# 20210410-JGaylord-Exprsn_MIDI.net
KiCad netlist of a schematic drawn in EAGLE
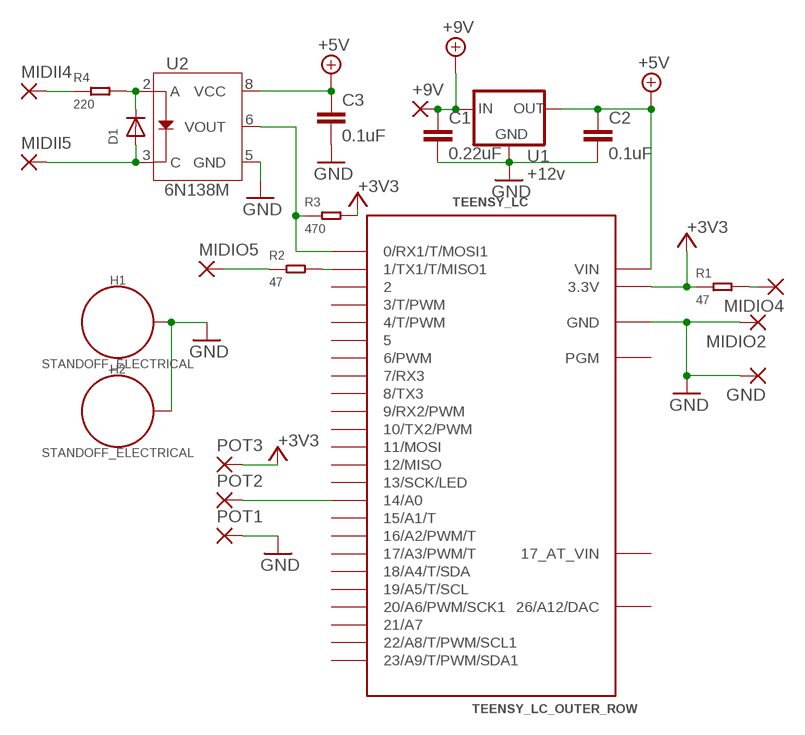
[diagram p0: schematic, sheet 1]

(export (version "E")
  (design (tool "Eeschema 10.0.6"))
  (components
    (comp (ref "+9V")
      (value "WIREPAD2,15/1,0")
      (footprint "eagle-import:2,15_1,0")
      (libsource (lib "eagle-import") (part "WIREPAD2,15/1,0"))
    )
    (comp (ref "C1")
      (value "0.22uF")
      (footprint "eagle-import:0603")
      (libsource (lib "eagle-import") (part "0.22UF-0603-25V-10%"))
    )
    (comp (ref "C2")
      (value "0.1uF")
      (footprint "eagle-import:0603")
      (libsource (lib "eagle-import") (part "0.1UF-0603-25V-(+80/-20%)"))
    )
    (comp (ref "C3")
      (value "0.1uF")
      (footprint "eagle-import:0603")
      (libsource (lib "eagle-import") (part "0.1UF-0603-25V-(+80/-20%)"))
    )
    (comp (ref "D1")
      (value "DIODESOD-123")
      (footprint "eagle-import:SOD-123")
      (libsource (lib "eagle-import") (part "DIODESOD-123"))
    )
    (comp (ref "GND")
      (value "WIREPAD2,15/1,0")
      (footprint "eagle-import:2,15_1,0")
      (libsource (lib "eagle-import") (part "WIREPAD2,15/1,0"))
    )
    (comp (ref "H1")
      (value "STANDOFF_ELECTRICAL")
      (footprint "eagle-import:STANDOFF-ELECTRICAL")
      (libsource (lib "eagle-import") (part "STANDOFF_ELECTRICAL"))
    )
    (comp (ref "H2")
      (value "STANDOFF_ELECTRICAL")
      (footprint "eagle-import:STANDOFF-ELECTRICAL")
      (libsource (lib "eagle-import") (part "STANDOFF_ELECTRICAL"))
    )
    (comp (ref "MIDII4")
      (value "WIREPAD2,15/1,0")
      (footprint "eagle-import:2,15_1,0")
      (libsource (lib "eagle-import") (part "WIREPAD2,15/1,0"))
    )
    (comp (ref "MIDII5")
      (value "WIREPAD2,15/1,0")
      (footprint "eagle-import:2,15_1,0")
      (libsource (lib "eagle-import") (part "WIREPAD2,15/1,0"))
    )
    (comp (ref "MIDIO2")
      (value "WIREPAD2,15/1,0")
      (footprint "eagle-import:2,15_1,0")
      (libsource (lib "eagle-import") (part "WIREPAD2,15/1,0"))
    )
    (comp (ref "MIDIO4")
      (value "WIREPAD2,15/1,0")
      (footprint "eagle-import:2,15_1,0")
      (libsource (lib "eagle-import") (part "WIREPAD2,15/1,0"))
    )
    (comp (ref "MIDIO5")
      (value "WIREPAD2,15/1,0")
      (footprint "eagle-import:2,15_1,0")
      (libsource (lib "eagle-import") (part "WIREPAD2,15/1,0"))
    )
    (comp (ref "POT1")
      (value "WIREPAD2,15/1,0")
      (footprint "eagle-import:2,15_1,0")
      (libsource (lib "eagle-import") (part "WIREPAD2,15/1,0"))
    )
    (comp (ref "POT2")
      (value "WIREPAD2,15/1,0")
      (footprint "eagle-import:2,15_1,0")
      (libsource (lib "eagle-import") (part "WIREPAD2,15/1,0"))
    )
    (comp (ref "POT3")
      (value "WIREPAD2,15/1,0")
      (footprint "eagle-import:2,15_1,0")
      (libsource (lib "eagle-import") (part "WIREPAD2,15/1,0"))
    )
    (comp (ref "R1")
      (value "47")
      (footprint "eagle-import:R0805")
      (fields (field (name "MPN") "RC0805JR-071KL"))
      (libsource (lib "eagle-import") (part "SMD-RES-0R-1%-1/8W(0805)"))
    )
    (comp (ref "R2")
      (value "47")
      (footprint "eagle-import:R0805")
      (fields (field (name "MPN") "RC0805JR-071KL"))
      (libsource (lib "eagle-import") (part "SMD-RES-0R-1%-1/8W(0805)"))
    )
    (comp (ref "R3")
      (value "470")
      (footprint "eagle-import:R0805")
      (fields (field (name "MPN") "RC0805JR-071KL"))
      (libsource (lib "eagle-import") (part "SMD-RES-0R-1%-1/8W(0805)"))
    )
    (comp (ref "R4")
      (value "220")
      (footprint "eagle-import:R0805")
      (fields (field (name "MPN") "RC0805JR-071KL"))
      (libsource (lib "eagle-import") (part "SMD-RES-0R-1%-1/8W(0805)"))
    )
    (comp (ref "TEENSY_LC")
      (value "TEENSY_LC_OUTER_ROW")
      (footprint "eagle-import:TEENSY_3.0-3.2&LC_OUTER_ROW")
      (libsource (lib "eagle-import") (part "TEENSY_LC_OUTER_ROW"))
    )
    (comp (ref "U1")
      (value "+12v")
      (footprint "eagle-import:TO-252")
      (libsource (lib "eagle-import") (part "V_REG_78XX7812"))
    )
    (comp (ref "U2")
      (value "6N138M")
      (footprint "eagle-import:8-SMD")
      (libsource (lib "eagle-import") (part "OPTO_DARL_6N138S"))
    )
  )
  (nets
    (net (code "1") (name "+3V3") (class "Default")
      (node (ref "POT3") (pin "1") (pinfunction "P_1") (pintype "passive"))
      (node (ref "R1") (pin "1") (pinfunction "1_1") (pintype "passive"))
      (node (ref "R3") (pin "2") (pinfunction "2_2") (pintype "passive"))
      (node (ref "TEENSY_LC") (pin "3.3V") (pinfunction "3.3V_3.3V") (pintype "power_in"))
      (node (ref "TEENSY_LC") (pin "3.3V1") (pinfunction "3.3V_3.3V1") (pintype "power_in"))
    )
    (net (code "2") (name "+5V") (class "Default")
      (node (ref "C2") (pin "1") (pinfunction "1_1") (pintype "passive"))
      (node (ref "C3") (pin "1") (pinfunction "1_1") (pintype "passive"))
      (node (ref "TEENSY_LC") (pin "VIN") (pinfunction "VIN_VIN") (pintype "power_in"))
      (node (ref "U1") (pin "2") (pinfunction "OUT_2") (pintype "passive"))
      (node (ref "U2") (pin "8") (pinfunction "VCC_8") (pintype "bidirectional"))
    )
    (net (code "3") (name "+9V") (class "Default")
      (node (ref "+9V") (pin "1") (pinfunction "P_1") (pintype "passive"))
      (node (ref "C1") (pin "1") (pinfunction "1_1") (pintype "passive"))
      (node (ref "U1") (pin "1") (pinfunction "IN_1") (pintype "input"))
    )
    (net (code "4") (name "/26{slash}A12{slash}DAC") (class "Default")
      (node (ref "TEENSY_LC") (pin "RESET/DAC") (pinfunction "26/A12/DAC_RESET/DAC") (pintype "power_in"))
    )
    (net (code "5") (name "GND") (class "Default")
      (node (ref "C1") (pin "2") (pinfunction "2_2") (pintype "passive"))
      (node (ref "C2") (pin "2") (pinfunction "2_2") (pintype "passive"))
      (node (ref "C3") (pin "2") (pinfunction "2_2") (pintype "passive"))
      (node (ref "GND") (pin "1") (pinfunction "P_1") (pintype "passive"))
      (node (ref "H1") (pin "P1") (pinfunction "P$1_P1") (pintype "bidirectional"))
      (node (ref "H2") (pin "P1") (pinfunction "P$1_P1") (pintype "bidirectional"))
      (node (ref "MIDIO2") (pin "1") (pinfunction "P_1") (pintype "passive"))
      (node (ref "POT1") (pin "1") (pinfunction "P_1") (pintype "passive"))
      (node (ref "TEENSY_LC") (pin "AGND") (pinfunction "GND_AGND") (pintype "power_in"))
      (node (ref "TEENSY_LC") (pin "GND") (pinfunction "GND_GND") (pintype "power_in"))
      (node (ref "TEENSY_LC") (pin "GND1") (pinfunction "GND_GND1") (pintype "power_in"))
      (node (ref "U1") (pin "3") (pinfunction "GND_3") (pintype "input"))
      (node (ref "U2") (pin "5") (pinfunction "GND_5") (pintype "bidirectional"))
    )
    (net (code "6") (name "Net-(MIDII4-P)") (class "Default")
      (node (ref "MIDII4") (pin "1") (pinfunction "P_1") (pintype "passive"))
      (node (ref "R4") (pin "1") (pinfunction "1_1") (pintype "passive"))
    )
    (net (code "7") (name "Net-(MIDII5-P)") (class "Default")
      (node (ref "D1") (pin "A") (pinfunction "A_A") (pintype "passive"))
      (node (ref "MIDII5") (pin "1") (pinfunction "P_1") (pintype "passive"))
      (node (ref "U2") (pin "3") (pinfunction "C_3") (pintype "bidirectional"))
    )
    (net (code "8") (name "Net-(MIDIO4-P)") (class "Default")
      (node (ref "MIDIO4") (pin "1") (pinfunction "P_1") (pintype "passive"))
      (node (ref "R1") (pin "2") (pinfunction "2_2") (pintype "passive"))
    )
    (net (code "9") (name "Net-(MIDIO5-P)") (class "Default")
      (node (ref "MIDIO5") (pin "1") (pinfunction "P_1") (pintype "passive"))
      (node (ref "R2") (pin "1") (pinfunction "1_1") (pintype "passive"))
    )
    (net (code "10") (name "Net-(POT2-P)") (class "Default")
      (node (ref "POT2") (pin "1") (pinfunction "P_1") (pintype "passive"))
      (node (ref "TEENSY_LC") (pin "14/A0") (pinfunction "14/A0_14/A0") (pintype "bidirectional"))
    )
    (net (code "11") (name "Net-(TEENSY_LC-0{slash}RX1{slash}T{slash}MOSI1)") (class "Default")
      (node (ref "R3") (pin "1") (pinfunction "1_1") (pintype "passive"))
      (node (ref "TEENSY_LC") (pin "0") (pinfunction "0/RX1/T/MOSI1_0") (pintype "bidirectional"))
      (node (ref "U2") (pin "6") (pinfunction "VOUT_6") (pintype "bidirectional"))
    )
    (net (code "12") (name "Net-(TEENSY_LC-1{slash}TX1{slash}T{slash}MISO1)") (class "Default")
      (node (ref "R2") (pin "2") (pinfunction "2_2") (pintype "passive"))
      (node (ref "TEENSY_LC") (pin "1") (pinfunction "1/TX1/T/MISO1_1") (pintype "bidirectional"))
    )
    (net (code "13") (name "Net-(U2-A)") (class "Default")
      (node (ref "D1") (pin "C") (pinfunction "C_C") (pintype "passive"))
      (node (ref "R4") (pin "2") (pinfunction "2_2") (pintype "passive"))
      (node (ref "U2") (pin "2") (pinfunction "A_2") (pintype "bidirectional"))
    )
    (net (code "14") (name "unconnected-(TEENSY_LC-3{slash}T{slash}PWM-Pad3)") (class "Default")
      (node (ref "TEENSY_LC") (pin "3") (pinfunction "3/T/PWM_3") (pintype "bidirectional"))
    )
    (net (code "15") (name "unconnected-(TEENSY_LC-4{slash}T{slash}PWM-Pad4)") (class "Default")
      (node (ref "TEENSY_LC") (pin "4") (pinfunction "4/T/PWM_4") (pintype "bidirectional"))
    )
    (net (code "16") (name "unconnected-(TEENSY_LC-6{slash}PWM-Pad6)") (class "Default")
      (node (ref "TEENSY_LC") (pin "6") (pinfunction "6/PWM_6") (pintype "bidirectional"))
    )
    (net (code "17") (name "unconnected-(TEENSY_LC-7{slash}RX3-Pad7)") (class "Default")
      (node (ref "TEENSY_LC") (pin "7") (pinfunction "7/RX3_7") (pintype "bidirectional"))
    )
    (net (code "18") (name "unconnected-(TEENSY_LC-8{slash}TX3-Pad8)") (class "Default")
      (node (ref "TEENSY_LC") (pin "8") (pinfunction "8/TX3_8") (pintype "bidirectional"))
    )
    (net (code "19") (name "unconnected-(TEENSY_LC-9{slash}RX2{slash}PWM-Pad9)") (class "Default")
      (node (ref "TEENSY_LC") (pin "9") (pinfunction "9/RX2/PWM_9") (pintype "bidirectional"))
    )
    (net (code "20") (name "unconnected-(TEENSY_LC-10{slash}TX2{slash}PWM-Pad10)") (class "Default")
      (node (ref "TEENSY_LC") (pin "10") (pinfunction "10/TX2/PWM_10") (pintype "bidirectional"))
    )
    (net (code "21") (name "unconnected-(TEENSY_LC-11{slash}MOSI-Pad11)") (class "Default")
      (node (ref "TEENSY_LC") (pin "11") (pinfunction "11/MOSI_11") (pintype "bidirectional"))
    )
    (net (code "22") (name "unconnected-(TEENSY_LC-12{slash}MISO-Pad12)") (class "Default")
      (node (ref "TEENSY_LC") (pin "12") (pinfunction "12/MISO_12") (pintype "bidirectional"))
    )
    (net (code "23") (name "unconnected-(TEENSY_LC-13{slash}SCK{slash}LED-Pad13)") (class "Default")
      (node (ref "TEENSY_LC") (pin "13") (pinfunction "13/SCK/LED_13") (pintype "bidirectional"))
    )
    (net (code "24") (name "unconnected-(TEENSY_LC-15{slash}A1{slash}T-Pad15{slash}A1)") (class "Default")
      (node (ref "TEENSY_LC") (pin "15/A1") (pinfunction "15/A1/T_15/A1") (pintype "bidirectional"))
    )
    (net (code "25") (name "unconnected-(TEENSY_LC-16{slash}A2{slash}PWM{slash}T-Pad16{slash}A2)") (class "Default")
      (node (ref "TEENSY_LC") (pin "16/A2") (pinfunction "16/A2/PWM/T_16/A2") (pintype "bidirectional"))
    )
    (net (code "26") (name "unconnected-(TEENSY_LC-17_AT_VIN-PadVBAT)") (class "Default")
      (node (ref "TEENSY_LC") (pin "VBAT") (pinfunction "17_AT_VIN_VBAT") (pintype "bidirectional"))
    )
    (net (code "27") (name "unconnected-(TEENSY_LC-17{slash}A3{slash}PWM{slash}T-Pad17{slash}A3)") (class "Default")
      (node (ref "TEENSY_LC") (pin "17/A3") (pinfunction "17/A3/PWM/T_17/A3") (pintype "bidirectional"))
    )
    (net (code "28") (name "unconnected-(TEENSY_LC-18{slash}A4{slash}T{slash}SDA-Pad18{slash}A4)") (class "Default")
      (node (ref "TEENSY_LC") (pin "18/A4") (pinfunction "18/A4/T/SDA_18/A4") (pintype "bidirectional"))
    )
    (net (code "29") (name "unconnected-(TEENSY_LC-19{slash}A5{slash}T{slash}SCL-Pad19{slash}A5)") (class "Default")
      (node (ref "TEENSY_LC") (pin "19/A5") (pinfunction "19/A5/T/SCL_19/A5") (pintype "bidirectional"))
    )
    (net (code "30") (name "unconnected-(TEENSY_LC-20{slash}A6{slash}PWM{slash}SCK1-Pad20{slash}A6)") (class "Default")
      (node (ref "TEENSY_LC") (pin "20/A6") (pinfunction "20/A6/PWM/SCK1_20/A6") (pintype "bidirectional"))
    )
    (net (code "31") (name "unconnected-(TEENSY_LC-22{slash}A8{slash}T{slash}PWM{slash}SCL1-Pad22{slash}A8)") (class "Default")
      (node (ref "TEENSY_LC") (pin "22/A8") (pinfunction "22/A8/T/PWM/SCL1_22/A8") (pintype "bidirectional"))
    )
    (net (code "32") (name "unconnected-(TEENSY_LC-23{slash}A9{slash}T{slash}PWM{slash}SDA1-Pad23{slash}A9)") (class "Default")
      (node (ref "TEENSY_LC") (pin "23/A9") (pinfunction "23/A9/T/PWM/SDA1_23/A9") (pintype "bidirectional"))
    )
    (net (code "33") (name "unconnected-(TEENSY_LC-Pad2)") (class "Default")
      (node (ref "TEENSY_LC") (pin "2") (pinfunction "2_2") (pintype "bidirectional"))
    )
    (net (code "34") (name "unconnected-(TEENSY_LC-Pad5)") (class "Default")
      (node (ref "TEENSY_LC") (pin "5") (pinfunction "5_5") (pintype "bidirectional"))
    )
    (net (code "35") (name "unconnected-(TEENSY_LC-Pad21{slash}A7)") (class "Default")
      (node (ref "TEENSY_LC") (pin "21/A7") (pinfunction "21/A7_21/A7") (pintype "bidirectional"))
    )
    (net (code "36") (name "unconnected-(TEENSY_LC-PadPGM)") (class "Default")
      (node (ref "TEENSY_LC") (pin "PGM") (pinfunction "PGM_PGM") (pintype "bidirectional"))
    )
  )
)
